# P15_Hi3531AV100_VO_I2S3.net
KiCad netlist of a schematic drawn in Altium Designer
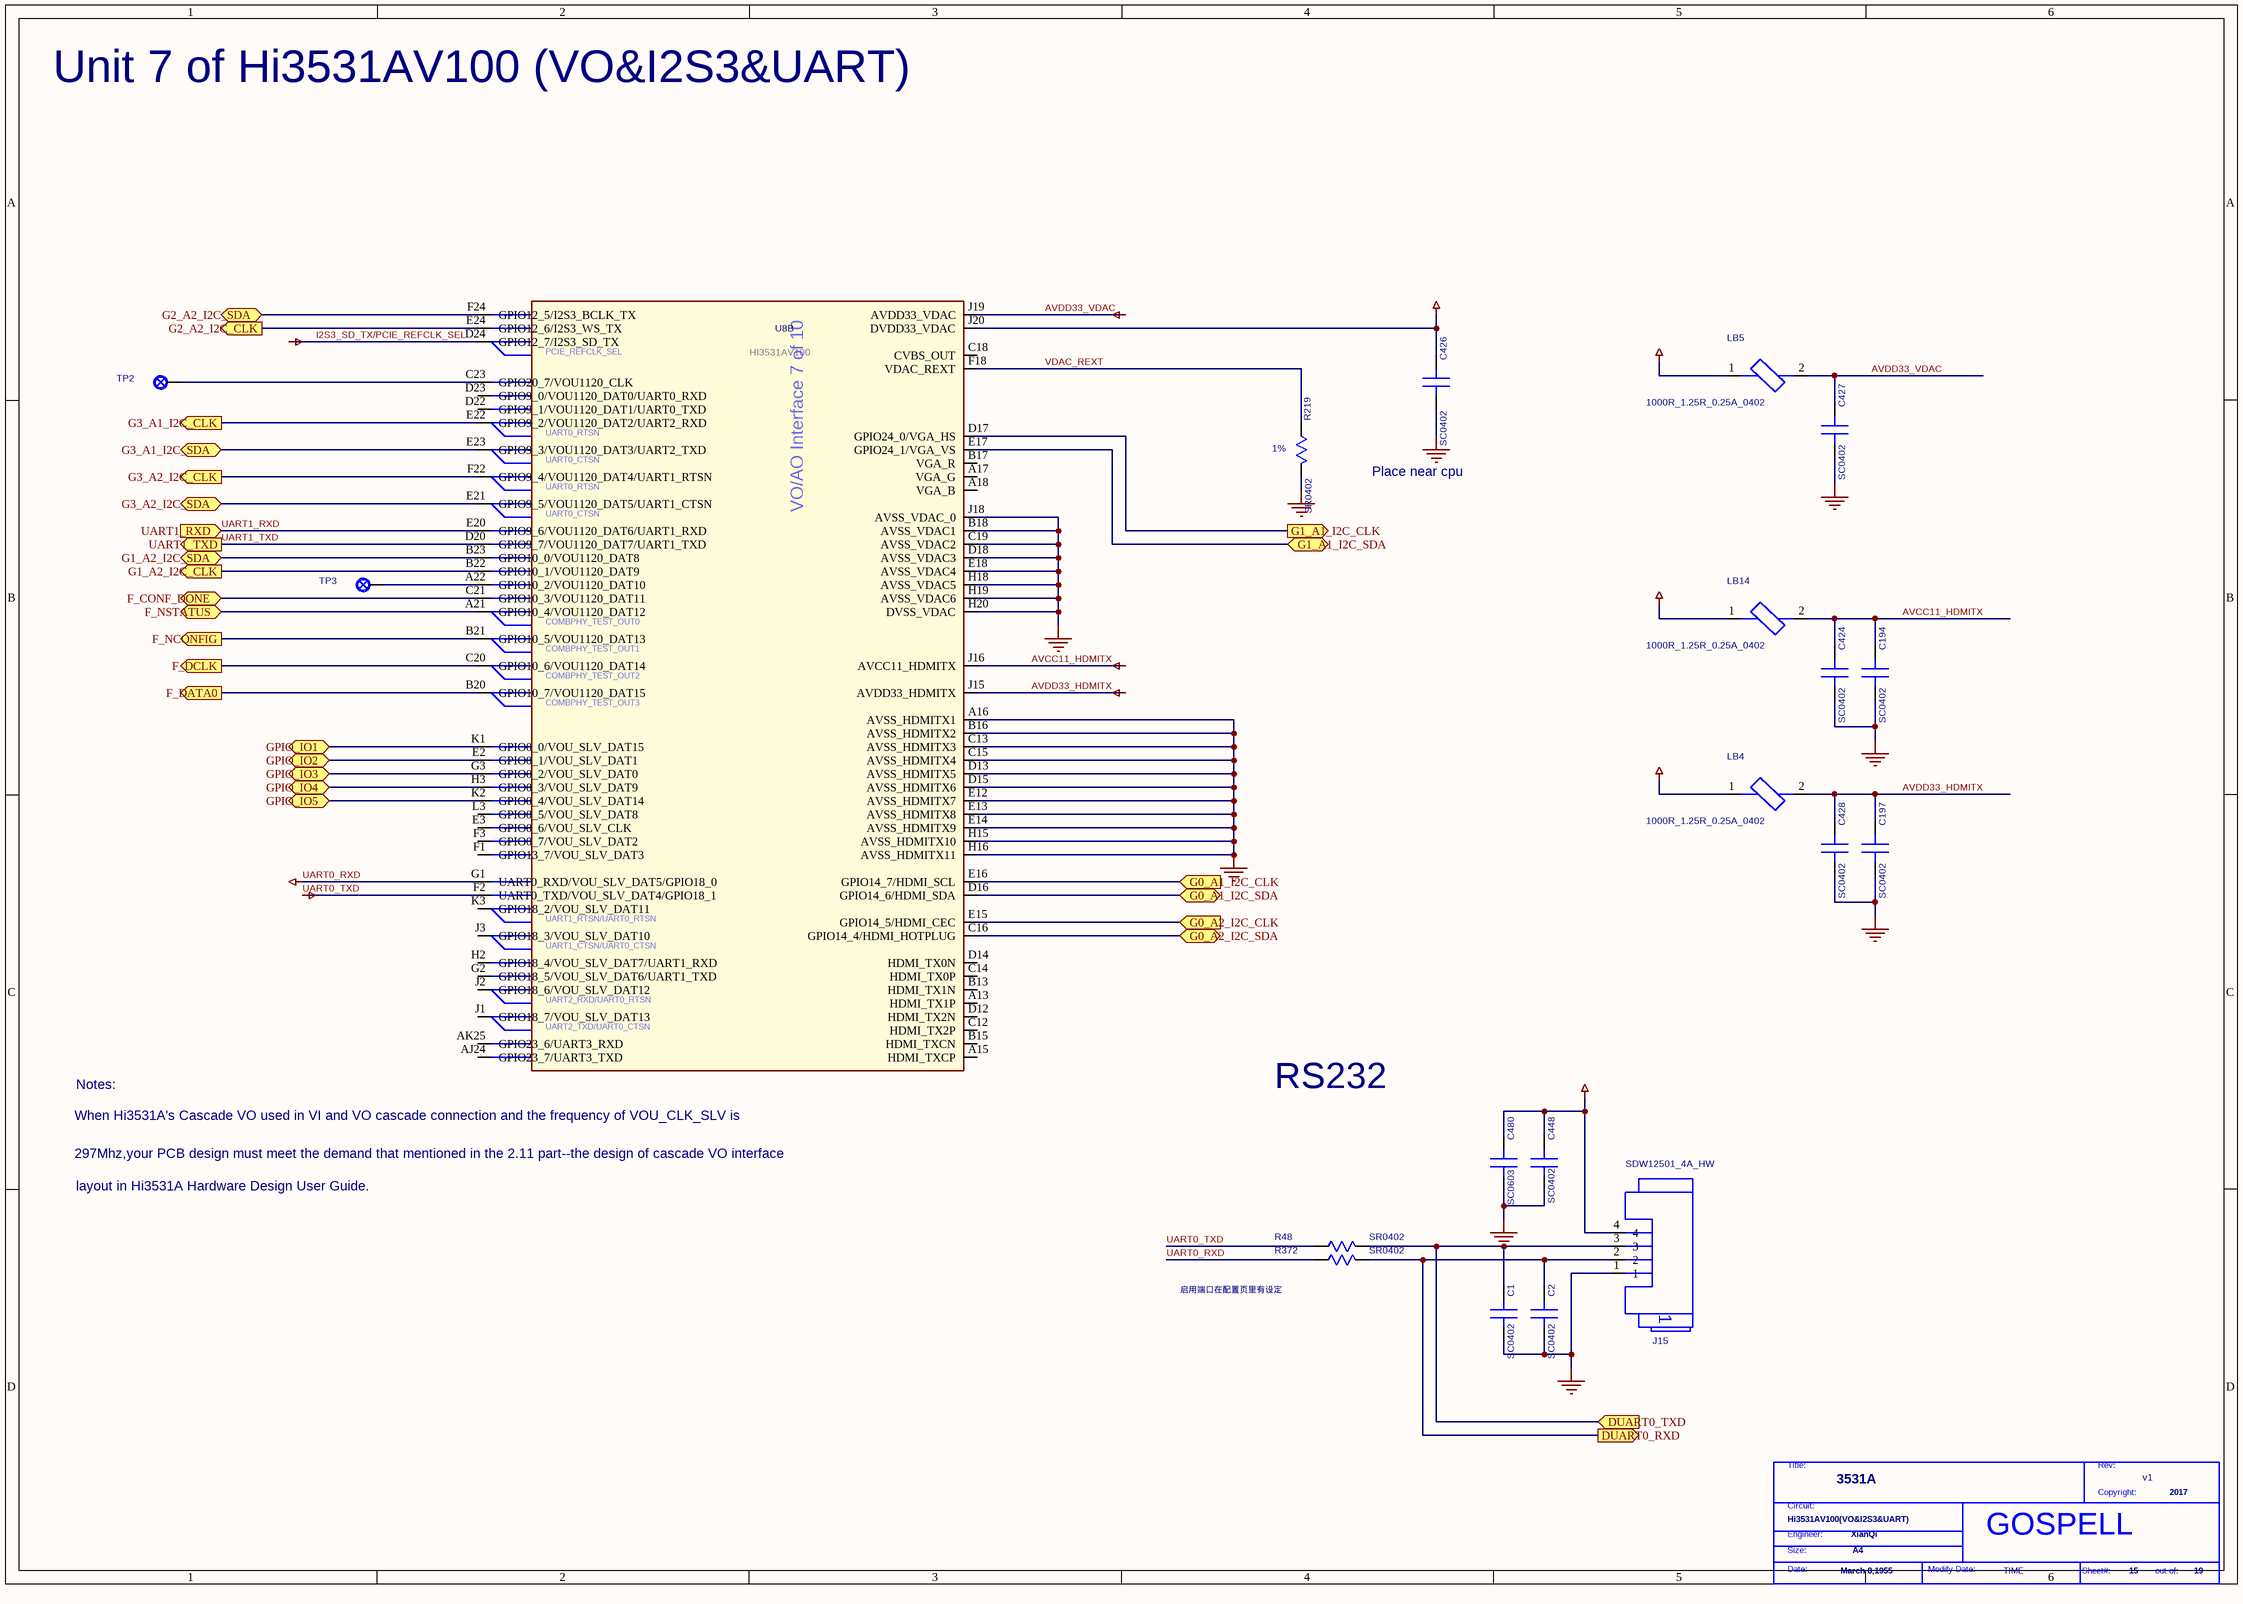
[diagram p0: P15 Hi3531AV100(VO&I2S3.SchDoc]

(export (version "E")
  (design (tool "Eeschema 10.0.6"))
  (components
    (comp (ref "C1") (value "SC0402") (libsource (lib "*") (part "C_0_Dup1")))
    (comp (ref "C2") (value "SC0402") (libsource (lib "*") (part "C_0_Dup1")))
    (comp (ref "C194") (value "SC0402") (libsource (lib "*") (part "C_0_Dup2")))
    (comp (ref "C197") (value "SC0402") (libsource (lib "*") (part "C_0_Dup2")))
    (comp (ref "C424") (value "SC0402") (libsource (lib "*") (part "C_0_Dup2")))
    (comp (ref "C426") (value "SC0402") (libsource (lib "*") (part "C_0_Dup2")))
    (comp (ref "C427") (value "SC0402") (libsource (lib "*") (part "C_0_Dup2")))
    (comp (ref "C428") (value "SC0402") (libsource (lib "*") (part "C_0_Dup2")))
    (comp (ref "C448") (value "SC0402") (libsource (lib "*") (part "C_0_Dup2")))
    (comp (ref "C480") (value "SC0603") (libsource (lib "*") (part "C_0_Dup2")))
    (comp (ref "J15")
      (value "4PIN-2.54")
      (fields (field (name "DEVICE") "SDW12501_4A_HW"))
      (libsource (lib "*") (part "WBC1X41_0"))
    )
    (comp (ref "LB4") (value "SL0402") (libsource (lib "*") (part "LB_0")))
    (comp (ref "LB5") (value "SL0402") (libsource (lib "*") (part "LB_0")))
    (comp (ref "LB14") (value "SL0402") (libsource (lib "*") (part "LB_0")))
    (comp (ref "R48") (value "SR0402") (libsource (lib "*") (part "R_1")))
    (comp (ref "R219") (value "SR0402") (libsource (lib "*") (part "R_1")))
    (comp (ref "R372") (value "SR0402") (libsource (lib "*") (part "R_1")))
    (comp (ref "TP2") (value "TP24-SMD") (libsource (lib "*") (part "TESTPOINT_0")))
    (comp (ref "TP3") (value "TP24-SMD") (libsource (lib "*") (part "TESTPOINT_0")))
    (comp (ref "U8")
      (value "BGA805-32-3333")
      (fields (field (name "DEVICE") "HI3531AV100"))
      (libsource (lib "*") (part "HI3531AV100_M2_17"))
    )
  )
  (nets
    (net (code "1") (name "/DUART0_RXD") (class "Default")
      (node (ref "C2") (pin "1") (pinfunction "A_1") (pintype "passive"))
      (node (ref "J15") (pin "2") (pinfunction "2_2") (pintype "passive"))
      (node (ref "R372") (pin "2") (pinfunction "B_2") (pintype "passive"))
    )
    (net (code "2") (name "/DUART0_TXD") (class "Default")
      (node (ref "C1") (pin "1") (pinfunction "A_1") (pintype "passive"))
      (node (ref "J15") (pin "3") (pinfunction "3_3") (pintype "passive"))
      (node (ref "R48") (pin "2") (pinfunction "B_2") (pintype "passive"))
    )
    (net (code "3") (name "/F_CONF_DONE") (class "Default")
      (node (ref "U8") (pin "C21") (pinfunction "GPIO10_3/VOU1120_DAT11_C21") (pintype "passive"))
    )
    (net (code "4") (name "/F_DATA0") (class "Default")
      (node (ref "U8") (pin "B20") (pinfunction "GPIO10_7/VOU1120_DAT15_B20") (pintype "passive"))
    )
    (net (code "5") (name "/F_DCLK") (class "Default")
      (node (ref "U8") (pin "C20") (pinfunction "GPIO10_6/VOU1120_DAT14_C20") (pintype "passive"))
    )
    (net (code "6") (name "/F_NCONFIG") (class "Default")
      (node (ref "U8") (pin "B21") (pinfunction "GPIO10_5/VOU1120_DAT13_B21") (pintype "passive"))
    )
    (net (code "7") (name "/F_NSTATUS") (class "Default")
      (node (ref "U8") (pin "A21") (pinfunction "GPIO10_4/VOU1120_DAT12_A21") (pintype "passive"))
    )
    (net (code "8") (name "/G0_A1_I2C_CLK") (class "Default")
      (node (ref "U8") (pin "E16") (pinfunction "GPIO14_7/HDMI_SCL_E16") (pintype "passive"))
    )
    (net (code "9") (name "/G0_A1_I2C_SDA") (class "Default")
      (node (ref "U8") (pin "D16") (pinfunction "GPIO14_6/HDMI_SDA_D16") (pintype "passive"))
    )
    (net (code "10") (name "/G0_A2_I2C_CLK") (class "Default")
      (node (ref "U8") (pin "E15") (pinfunction "GPIO14_5/HDMI_CEC_E15") (pintype "passive"))
    )
    (net (code "11") (name "/G0_A2_I2C_SDA") (class "Default")
      (node (ref "U8") (pin "C16") (pinfunction "GPIO14_4/HDMI_HOTPLUG_C16") (pintype "passive"))
    )
    (net (code "12") (name "/G1_A1_I2C_CLK") (class "Default")
      (node (ref "U8") (pin "D17") (pinfunction "GPIO24_0/VGA_HS_D17") (pintype "passive"))
    )
    (net (code "13") (name "/G1_A1_I2C_SDA") (class "Default")
      (node (ref "U8") (pin "E17") (pinfunction "GPIO24_1/VGA_VS_E17") (pintype "passive"))
    )
    (net (code "14") (name "/G1_A2_I2C_CLK") (class "Default")
      (node (ref "U8") (pin "B22") (pinfunction "GPIO10_1/VOU1120_DAT9_B22") (pintype "passive"))
    )
    (net (code "15") (name "/G1_A2_I2C_SDA") (class "Default")
      (node (ref "U8") (pin "B23") (pinfunction "GPIO10_0/VOU1120_DAT8_B23") (pintype "passive"))
    )
    (net (code "16") (name "/G2_A2_I2C_CLK") (class "Default")
      (node (ref "U8") (pin "E24") (pinfunction "GPIO12_6/I2S3_WS_TX_E24") (pintype "passive"))
    )
    (net (code "17") (name "/G2_A2_I2C_SDA") (class "Default")
      (node (ref "U8") (pin "F24") (pinfunction "GPIO12_5/I2S3_BCLK_TX_F24") (pintype "passive"))
    )
    (net (code "18") (name "/G3_A1_I2C_CLK") (class "Default")
      (node (ref "U8") (pin "E22") (pinfunction "GPIO9_2/VOU1120_DAT2/UART2_RXD_E22") (pintype "passive"))
    )
    (net (code "19") (name "/G3_A1_I2C_SDA") (class "Default")
      (node (ref "U8") (pin "E23") (pinfunction "GPIO9_3/VOU1120_DAT3/UART2_TXD_E23") (pintype "passive"))
    )
    (net (code "20") (name "/G3_A2_I2C_CLK") (class "Default")
      (node (ref "U8") (pin "F22") (pinfunction "GPIO9_4/VOU1120_DAT4/UART1_RTSN_F22") (pintype "passive"))
    )
    (net (code "21") (name "/G3_A2_I2C_SDA") (class "Default")
      (node (ref "U8") (pin "E21") (pinfunction "GPIO9_5/VOU1120_DAT5/UART1_CTSN_E21") (pintype "passive"))
    )
    (net (code "22") (name "/GPIO_IO1") (class "Default")
      (node (ref "U8") (pin "K1") (pinfunction "GPIO0_0/VOU_SLV_DAT15_K1") (pintype "passive"))
    )
    (net (code "23") (name "/GPIO_IO2") (class "Default")
      (node (ref "U8") (pin "E2") (pinfunction "GPIO0_1/VOU_SLV_DAT1_E2") (pintype "passive"))
    )
    (net (code "24") (name "/GPIO_IO3") (class "Default")
      (node (ref "U8") (pin "G3") (pinfunction "GPIO0_2/VOU_SLV_DAT0_G3") (pintype "passive"))
    )
    (net (code "25") (name "/GPIO_IO4") (class "Default")
      (node (ref "U8") (pin "H3") (pinfunction "GPIO0_3/VOU_SLV_DAT9_H3") (pintype "passive"))
    )
    (net (code "26") (name "/GPIO_IO5") (class "Default")
      (node (ref "U8") (pin "K2") (pinfunction "GPIO0_4/VOU_SLV_DAT14_K2") (pintype "passive"))
    )
    (net (code "27") (name "/UART1_RXD") (class "Default")
      (node (ref "U8") (pin "E20") (pinfunction "GPIO9_6/VOU1120_DAT6/UART1_RXD_E20") (pintype "passive"))
    )
    (net (code "28") (name "/UART1_TXD") (class "Default")
      (node (ref "U8") (pin "D20") (pinfunction "GPIO9_7/VOU1120_DAT7/UART1_TXD_D20") (pintype "passive"))
    )
    (net (code "29") (name "/VDAC_REXT") (class "Default")
      (node (ref "R219") (pin "1") (pinfunction "A_1") (pintype "passive"))
      (node (ref "U8") (pin "F18") (pinfunction "VDAC_REXT_F18") (pintype "passive"))
    )
    (net (code "30") (name "3V3") (class "Default")
      (node (ref "C426") (pin "1") (pinfunction "A_1") (pintype "passive"))
      (node (ref "C448") (pin "1") (pinfunction "A_1") (pintype "passive"))
      (node (ref "C480") (pin "1") (pinfunction "A_1") (pintype "passive"))
      (node (ref "J15") (pin "4") (pinfunction "4_4") (pintype "passive"))
      (node (ref "LB4") (pin "1") (pinfunction "1_1") (pintype "passive"))
      (node (ref "LB5") (pin "1") (pinfunction "1_1") (pintype "passive"))
      (node (ref "U8") (pin "J20") (pinfunction "DVDD33_VDAC_J20") (pintype "passive"))
    )
    (net (code "31") (name "AVCC11_HDMITX") (class "Default")
      (node (ref "C194") (pin "1") (pinfunction "A_1") (pintype "passive"))
      (node (ref "C424") (pin "1") (pinfunction "A_1") (pintype "passive"))
      (node (ref "LB14") (pin "2") (pinfunction "2_2") (pintype "passive"))
      (node (ref "U8") (pin "J16") (pinfunction "AVCC11_HDMITX_J16") (pintype "passive"))
    )
    (net (code "32") (name "AVDD33_HDMITX") (class "Default")
      (node (ref "C197") (pin "1") (pinfunction "A_1") (pintype "passive"))
      (node (ref "C428") (pin "1") (pinfunction "A_1") (pintype "passive"))
      (node (ref "LB4") (pin "2") (pinfunction "2_2") (pintype "passive"))
      (node (ref "U8") (pin "J15") (pinfunction "AVDD33_HDMITX_J15") (pintype "passive"))
    )
    (net (code "33") (name "AVDD33_VDAC") (class "Default")
      (node (ref "C427") (pin "1") (pinfunction "A_1") (pintype "passive"))
      (node (ref "LB5") (pin "2") (pinfunction "2_2") (pintype "passive"))
      (node (ref "U8") (pin "J19") (pinfunction "AVDD33_VDAC_J19") (pintype "passive"))
    )
    (net (code "34") (name "DVDD_CORE") (class "Default")
      (node (ref "LB14") (pin "1") (pinfunction "1_1") (pintype "passive"))
    )
    (net (code "35") (name "GND") (class "Default")
      (node (ref "C1") (pin "2") (pinfunction "B_2") (pintype "passive"))
      (node (ref "C194") (pin "2") (pinfunction "B_2") (pintype "passive"))
      (node (ref "C197") (pin "2") (pinfunction "B_2") (pintype "passive"))
      (node (ref "C2") (pin "2") (pinfunction "B_2") (pintype "passive"))
      (node (ref "C424") (pin "2") (pinfunction "B_2") (pintype "passive"))
      (node (ref "C426") (pin "2") (pinfunction "B_2") (pintype "passive"))
      (node (ref "C427") (pin "2") (pinfunction "B_2") (pintype "passive"))
      (node (ref "C428") (pin "2") (pinfunction "B_2") (pintype "passive"))
      (node (ref "C448") (pin "2") (pinfunction "B_2") (pintype "passive"))
      (node (ref "C480") (pin "2") (pinfunction "B_2") (pintype "passive"))
      (node (ref "J15") (pin "1") (pinfunction "1_1") (pintype "passive"))
      (node (ref "R219") (pin "2") (pinfunction "B_2") (pintype "passive"))
      (node (ref "U8") (pin "A16") (pinfunction "AVSS_HDMITX1_A16") (pintype "passive"))
      (node (ref "U8") (pin "B16") (pinfunction "AVSS_HDMITX2_B16") (pintype "passive"))
      (node (ref "U8") (pin "B18") (pinfunction "AVSS_VDAC1_B18") (pintype "passive"))
      (node (ref "U8") (pin "C13") (pinfunction "AVSS_HDMITX3_C13") (pintype "passive"))
      (node (ref "U8") (pin "C15") (pinfunction "AVSS_HDMITX4_C15") (pintype "passive"))
      (node (ref "U8") (pin "C19") (pinfunction "AVSS_VDAC2_C19") (pintype "passive"))
      (node (ref "U8") (pin "D13") (pinfunction "AVSS_HDMITX5_D13") (pintype "passive"))
      (node (ref "U8") (pin "D15") (pinfunction "AVSS_HDMITX6_D15") (pintype "passive"))
      (node (ref "U8") (pin "D18") (pinfunction "AVSS_VDAC3_D18") (pintype "passive"))
      (node (ref "U8") (pin "E12") (pinfunction "AVSS_HDMITX7_E12") (pintype "passive"))
      (node (ref "U8") (pin "E13") (pinfunction "AVSS_HDMITX8_E13") (pintype "passive"))
      (node (ref "U8") (pin "E14") (pinfunction "AVSS_HDMITX9_E14") (pintype "passive"))
      (node (ref "U8") (pin "E18") (pinfunction "AVSS_VDAC4_E18") (pintype "passive"))
      (node (ref "U8") (pin "H15") (pinfunction "AVSS_HDMITX10_H15") (pintype "passive"))
      (node (ref "U8") (pin "H16") (pinfunction "AVSS_HDMITX11_H16") (pintype "passive"))
      (node (ref "U8") (pin "H18") (pinfunction "AVSS_VDAC5_H18") (pintype "passive"))
      (node (ref "U8") (pin "H19") (pinfunction "AVSS_VDAC6_H19") (pintype "passive"))
      (node (ref "U8") (pin "H20") (pinfunction "DVSS_VDAC_H20") (pintype "passive"))
      (node (ref "U8") (pin "J18") (pinfunction "AVSS_VDAC_0_J18") (pintype "passive"))
    )
    (net (code "36") (name "I2S3_SD_TX{slash}PCIE_REFCLK_SEL") (class "Default")
      (node (ref "U8") (pin "D24") (pinfunction "GPIO12_7/I2S3_SD_TX_D24") (pintype "passive"))
    )
    (net (code "37") (name "Net-(U8B-GPIO10_2{slash}VOU1120_DAT10)") (class "Default")
      (node (ref "TP3") (pin "1") (pinfunction "1_1") (pintype "passive"))
      (node (ref "U8") (pin "A22") (pinfunction "GPIO10_2/VOU1120_DAT10_A22") (pintype "passive"))
    )
    (net (code "38") (name "Net-(U8B-GPIO20_7{slash}VOU1120_CLK)") (class "Default")
      (node (ref "TP2") (pin "1") (pinfunction "1_1") (pintype "passive"))
      (node (ref "U8") (pin "C23") (pinfunction "GPIO20_7/VOU1120_CLK_C23") (pintype "passive"))
    )
    (net (code "39") (name "UART0_RXD") (class "Default")
      (node (ref "R372") (pin "1") (pinfunction "A_1") (pintype "passive"))
      (node (ref "U8") (pin "G1") (pinfunction "UART0_RXD/VOU_SLV_DAT5/GPIO18_0_G1") (pintype "passive"))
    )
    (net (code "40") (name "UART0_TXD") (class "Default")
      (node (ref "R48") (pin "1") (pinfunction "A_1") (pintype "passive"))
      (node (ref "U8") (pin "F2") (pinfunction "UART0_TXD/VOU_SLV_DAT4/GPIO18_1_F2") (pintype "passive"))
    )
    (net (code "41") (name "unconnected-(U8B-CVBS_OUT-PadC18)") (class "Default")
      (node (ref "U8") (pin "C18") (pinfunction "CVBS_OUT_C18") (pintype "passive"))
    )
    (net (code "42") (name "unconnected-(U8B-GPIO0_5{slash}VOU_SLV_DAT8-PadL3)") (class "Default")
      (node (ref "U8") (pin "L3") (pinfunction "GPIO0_5/VOU_SLV_DAT8_L3") (pintype "passive"))
    )
    (net (code "43") (name "unconnected-(U8B-GPIO0_6{slash}VOU_SLV_CLK-PadE3)") (class "Default")
      (node (ref "U8") (pin "E3") (pinfunction "GPIO0_6/VOU_SLV_CLK_E3") (pintype "passive"))
    )
    (net (code "44") (name "unconnected-(U8B-GPIO0_7{slash}VOU_SLV_DAT2-PadF3)") (class "Default")
      (node (ref "U8") (pin "F3") (pinfunction "GPIO0_7/VOU_SLV_DAT2_F3") (pintype "passive"))
    )
    (net (code "45") (name "unconnected-(U8B-GPIO9_0{slash}VOU1120_DAT0{slash}UART0_RXD-PadD23)") (class "Default")
      (node (ref "U8") (pin "D23") (pinfunction "GPIO9_0/VOU1120_DAT0/UART0_RXD_D23") (pintype "passive"))
    )
    (net (code "46") (name "unconnected-(U8B-GPIO9_1{slash}VOU1120_DAT1{slash}UART0_TXD-PadD22)") (class "Default")
      (node (ref "U8") (pin "D22") (pinfunction "GPIO9_1/VOU1120_DAT1/UART0_TXD_D22") (pintype "passive"))
    )
    (net (code "47") (name "unconnected-(U8B-GPIO13_7{slash}VOU_SLV_DAT3-PadF1)") (class "Default")
      (node (ref "U8") (pin "F1") (pinfunction "GPIO13_7/VOU_SLV_DAT3_F1") (pintype "passive"))
    )
    (net (code "48") (name "unconnected-(U8B-GPIO18_2{slash}VOU_SLV_DAT11-PadK3)") (class "Default")
      (node (ref "U8") (pin "K3") (pinfunction "GPIO18_2/VOU_SLV_DAT11_K3") (pintype "passive"))
    )
    (net (code "49") (name "unconnected-(U8B-GPIO18_3{slash}VOU_SLV_DAT10-PadJ3)") (class "Default")
      (node (ref "U8") (pin "J3") (pinfunction "GPIO18_3/VOU_SLV_DAT10_J3") (pintype "passive"))
    )
    (net (code "50") (name "unconnected-(U8B-GPIO18_4{slash}VOU_SLV_DAT7{slash}UART1_RXD-PadH2)") (class "Default")
      (node (ref "U8") (pin "H2") (pinfunction "GPIO18_4/VOU_SLV_DAT7/UART1_RXD_H2") (pintype "passive"))
    )
    (net (code "51") (name "unconnected-(U8B-GPIO18_5{slash}VOU_SLV_DAT6{slash}UART1_TXD-PadG2)") (class "Default")
      (node (ref "U8") (pin "G2") (pinfunction "GPIO18_5/VOU_SLV_DAT6/UART1_TXD_G2") (pintype "passive"))
    )
    (net (code "52") (name "unconnected-(U8B-GPIO18_6{slash}VOU_SLV_DAT12-PadJ2)") (class "Default")
      (node (ref "U8") (pin "J2") (pinfunction "GPIO18_6/VOU_SLV_DAT12_J2") (pintype "passive"))
    )
    (net (code "53") (name "unconnected-(U8B-GPIO18_7{slash}VOU_SLV_DAT13-PadJ1)") (class "Default")
      (node (ref "U8") (pin "J1") (pinfunction "GPIO18_7/VOU_SLV_DAT13_J1") (pintype "passive"))
    )
    (net (code "54") (name "unconnected-(U8B-GPIO23_6{slash}UART3_RXD-PadAK25)") (class "Default")
      (node (ref "U8") (pin "AK25") (pinfunction "GPIO23_6/UART3_RXD_AK25") (pintype "passive"))
    )
    (net (code "55") (name "unconnected-(U8B-GPIO23_7{slash}UART3_TXD-PadAJ24)") (class "Default")
      (node (ref "U8") (pin "AJ24") (pinfunction "GPIO23_7/UART3_TXD_AJ24") (pintype "passive"))
    )
    (net (code "56") (name "unconnected-(U8B-HDMI_TX0N-PadD14)") (class "Default")
      (node (ref "U8") (pin "D14") (pinfunction "HDMI_TX0N_D14") (pintype "passive"))
    )
    (net (code "57") (name "unconnected-(U8B-HDMI_TX0P-PadC14)") (class "Default")
      (node (ref "U8") (pin "C14") (pinfunction "HDMI_TX0P_C14") (pintype "passive"))
    )
    (net (code "58") (name "unconnected-(U8B-HDMI_TX1N-PadB13)") (class "Default")
      (node (ref "U8") (pin "B13") (pinfunction "HDMI_TX1N_B13") (pintype "passive"))
    )
    (net (code "59") (name "unconnected-(U8B-HDMI_TX1P-PadA13)") (class "Default")
      (node (ref "U8") (pin "A13") (pinfunction "HDMI_TX1P_A13") (pintype "passive"))
    )
    (net (code "60") (name "unconnected-(U8B-HDMI_TX2N-PadD12)") (class "Default")
      (node (ref "U8") (pin "D12") (pinfunction "HDMI_TX2N_D12") (pintype "passive"))
    )
    (net (code "61") (name "unconnected-(U8B-HDMI_TX2P-PadC12)") (class "Default")
      (node (ref "U8") (pin "C12") (pinfunction "HDMI_TX2P_C12") (pintype "passive"))
    )
    (net (code "62") (name "unconnected-(U8B-HDMI_TXCN-PadB15)") (class "Default")
      (node (ref "U8") (pin "B15") (pinfunction "HDMI_TXCN_B15") (pintype "passive"))
    )
    (net (code "63") (name "unconnected-(U8B-HDMI_TXCP-PadA15)") (class "Default")
      (node (ref "U8") (pin "A15") (pinfunction "HDMI_TXCP_A15") (pintype "passive"))
    )
    (net (code "64") (name "unconnected-(U8B-VGA_B-PadA18)") (class "Default")
      (node (ref "U8") (pin "A18") (pinfunction "VGA_B_A18") (pintype "passive"))
    )
    (net (code "65") (name "unconnected-(U8B-VGA_G-PadA17)") (class "Default")
      (node (ref "U8") (pin "A17") (pinfunction "VGA_G_A17") (pintype "passive"))
    )
    (net (code "66") (name "unconnected-(U8B-VGA_R-PadB17)") (class "Default")
      (node (ref "U8") (pin "B17") (pinfunction "VGA_R_B17") (pintype "passive"))
    )
  )
)
